# ATSAMD21G18A.net
KiCad netlist of a schematic drawn in Altium Designer
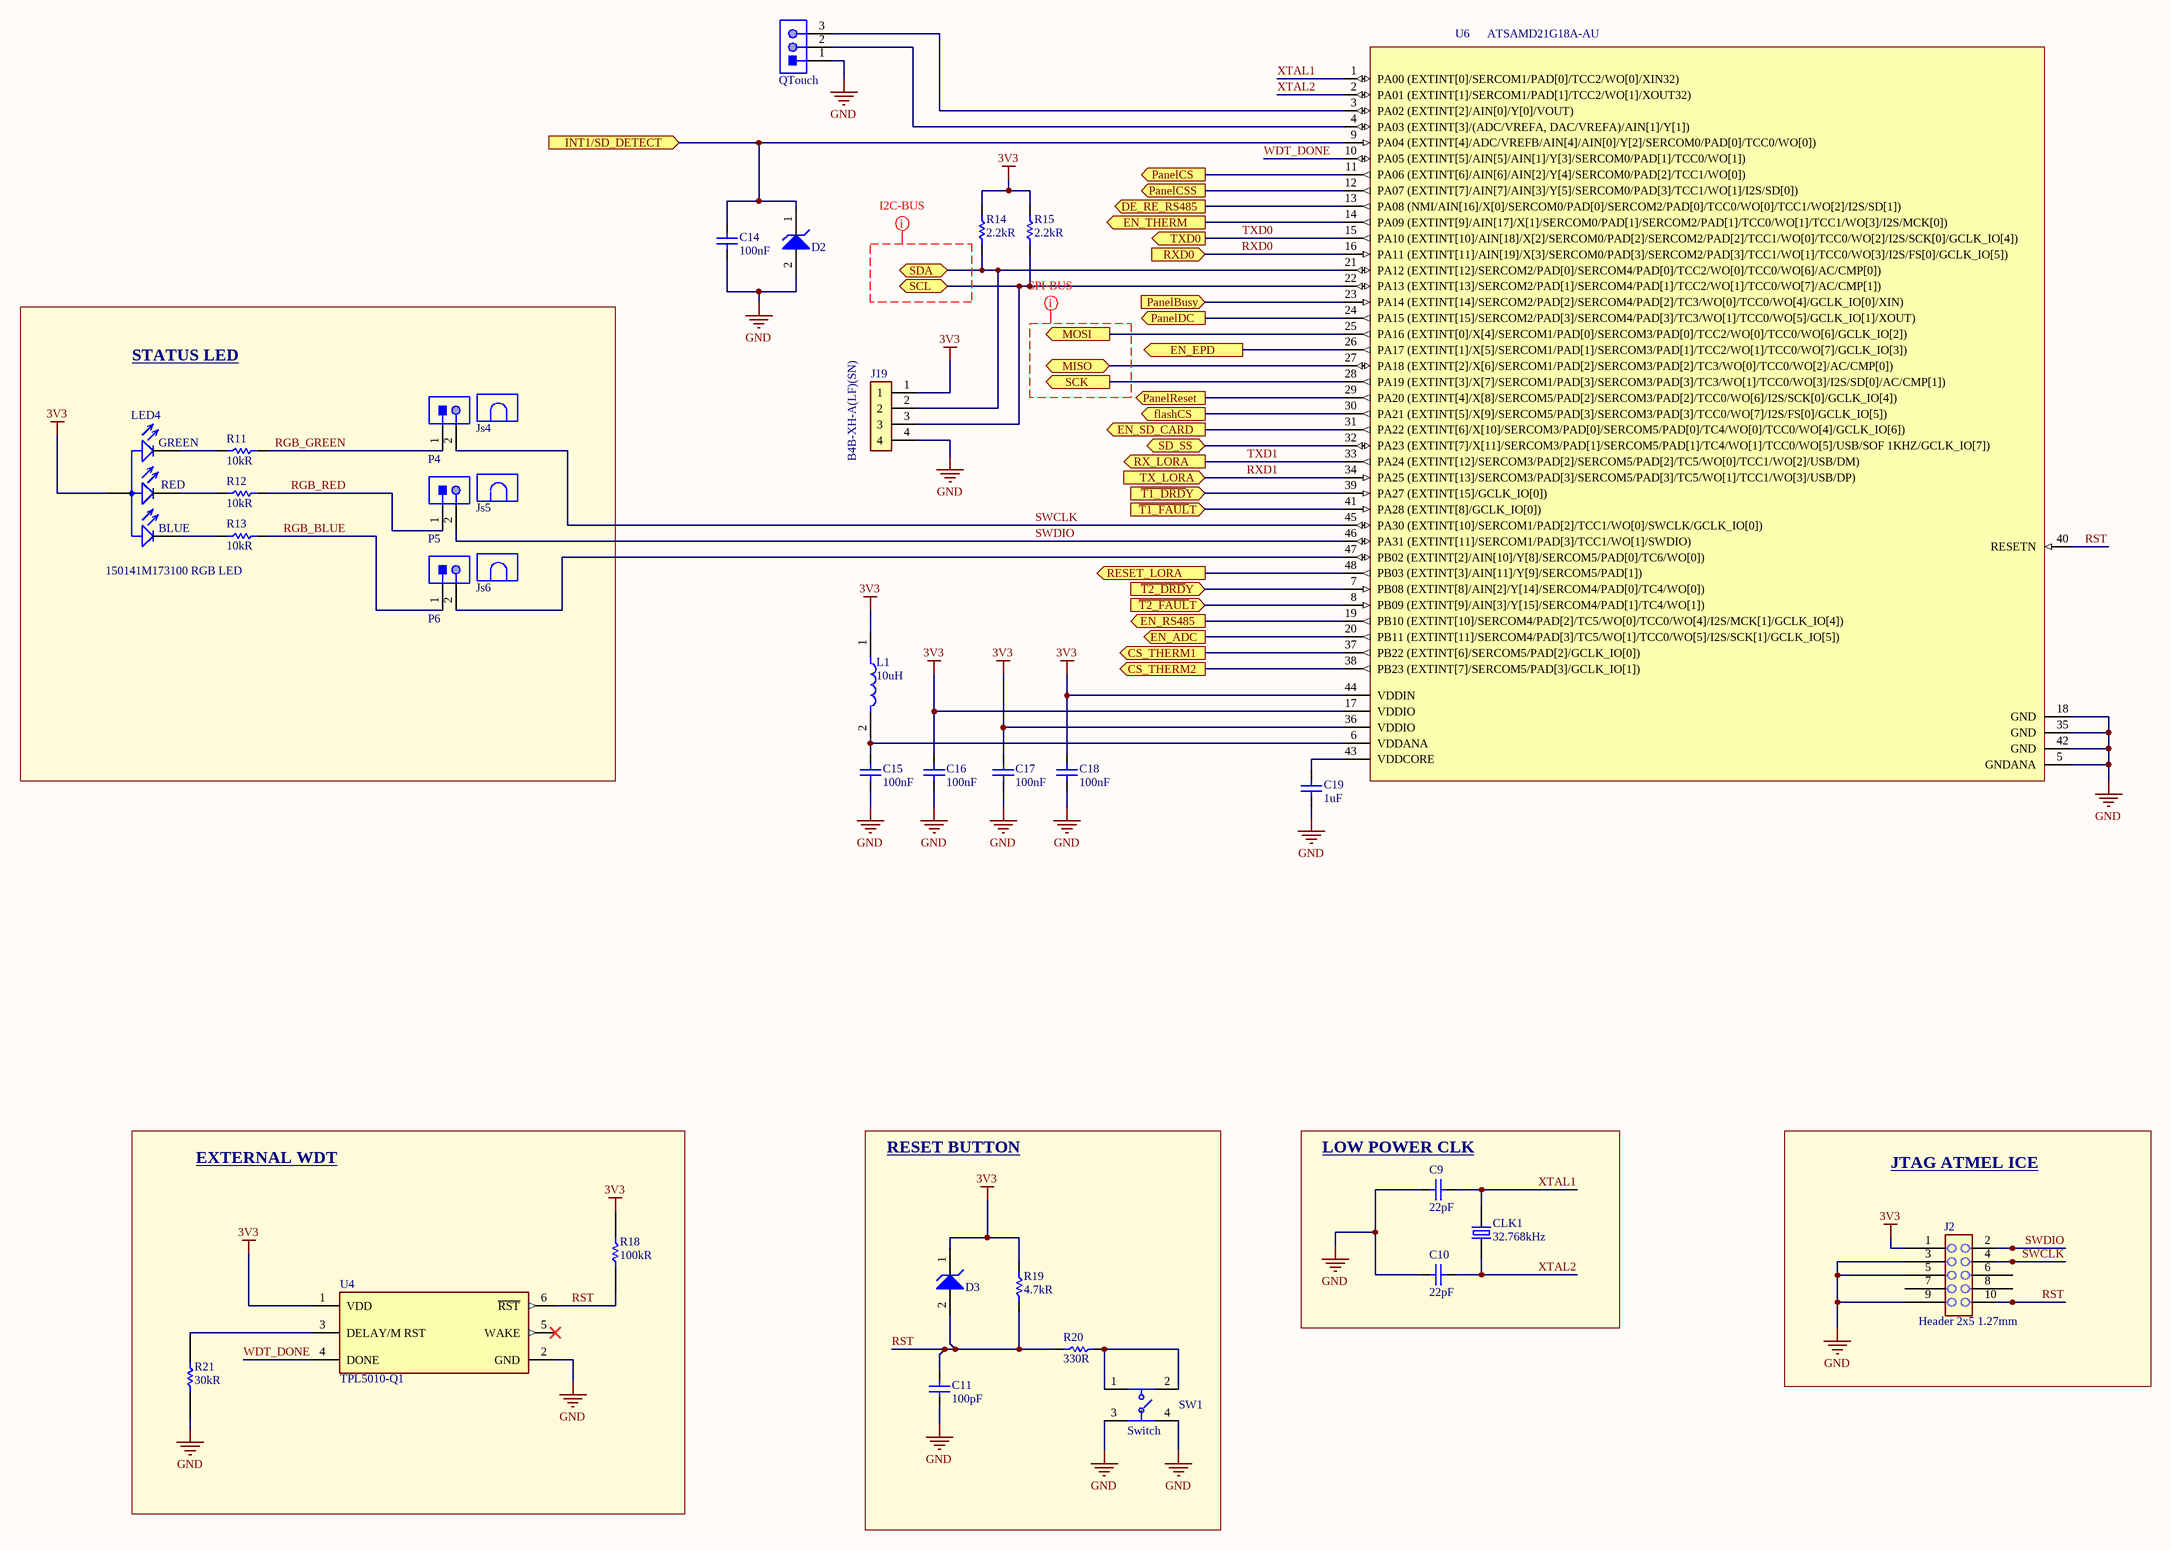
[diagram p0: ATSAMD21G18A.SchDoc]

(export (version "E")
  (design (tool "Eeschema 10.0.6"))
  (components
    (comp (ref "C9")
      (value "22pF")
      (footprint "Cap 0805 (2012 Metric)")
      (description "Capacitor; Ceramic; Cap; 22.0pF; Tol 5%; SMT; Vol-Rtg 50V; C0G; Tape and Reel")
      (fields
        (field (name "MANUFACTURER") "KEMET")
        (field (name "MANUFACTURER PART NUMBER") "C0805C220J5GACTU")
      )
      (libsource (lib "Daniel_Integrated_Library") (part "Capacitor"))
    )
    (comp (ref "C10")
      (value "22pF")
      (footprint "Cap 0805 (2012 Metric)")
      (description "Capacitor; Ceramic; Cap; 22.0pF; Tol 5%; SMT; Vol-Rtg 50V; C0G; Tape and Reel")
      (fields
        (field (name "MANUFACTURER") "KEMET")
        (field (name "MANUFACTURER PART NUMBER") "C0805C220J5GACTU")
      )
      (libsource (lib "Daniel_Integrated_Library") (part "Capacitor"))
    )
    (comp (ref "C11")
      (value "100pF")
      (footprint "Cap 0805 (2012 Metric)")
      (fields
        (field (name "MANUFACTURER") "KEMET")
        (field (name "MANUFACTURER PART NUMBER") "C0805C101J5GACTU")
        (field (name "TOLERANCE") "5%")
      )
      (libsource (lib "Daniel_Integrated_Library") (part "Capacitor"))
    )
    (comp (ref "C14")
      (value "100nF")
      (footprint "Cap 0805 (2012 Metric)")
      (fields
        (field (name "MANUFACTURER") "Yageo")
        (field (name "MANUFACTURER PART NUMBER") "CC0805ZRY5V9BB104")
        (field (name "TOLERANCE") "80%")
      )
      (libsource (lib "Daniel_Integrated_Library") (part "Capacitor"))
    )
    (comp (ref "C15")
      (value "100nF")
      (footprint "Cap 0805 (2012 Metric)")
      (fields
        (field (name "MANUFACTURER") "Yageo")
        (field (name "MANUFACTURER PART NUMBER") "CC0805ZRY5V9BB104")
        (field (name "TOLERANCE") "80%")
      )
      (libsource (lib "Daniel_Integrated_Library") (part "Capacitor"))
    )
    (comp (ref "C16")
      (value "100nF")
      (footprint "Cap 0805 (2012 Metric)")
      (fields
        (field (name "MANUFACTURER") "Yageo")
        (field (name "MANUFACTURER PART NUMBER") "CC0805ZRY5V9BB104")
        (field (name "TOLERANCE") "80%")
      )
      (libsource (lib "Daniel_Integrated_Library") (part "Capacitor"))
    )
    (comp (ref "C17")
      (value "100nF")
      (footprint "Cap 0805 (2012 Metric)")
      (fields
        (field (name "MANUFACTURER") "Yageo")
        (field (name "MANUFACTURER PART NUMBER") "CC0805ZRY5V9BB104")
        (field (name "TOLERANCE") "80%")
      )
      (libsource (lib "Daniel_Integrated_Library") (part "Capacitor"))
    )
    (comp (ref "C18")
      (value "100nF")
      (footprint "Cap 0805 (2012 Metric)")
      (fields
        (field (name "MANUFACTURER") "Yageo")
        (field (name "MANUFACTURER PART NUMBER") "CC0805ZRY5V9BB104")
        (field (name "TOLERANCE") "80%")
      )
      (libsource (lib "Daniel_Integrated_Library") (part "Capacitor"))
    )
    (comp (ref "C19")
      (value "1uF")
      (footprint "Cap 0805 (2012 Metric)")
      (description "Ceramic capacitor SMD-0805 1000nF /16V X7R# K +-10%, Samsung, RoHS/3000pcs/")
      (fields
        (field (name "MANUFACTURER") "Samsung")
        (field (name "MANUFACTURER PART NUMBER") "CL21B105KOFNNNG")
      )
      (libsource (lib "Daniel_Integrated_Library") (part "Capacitor"))
    )
    (comp (ref "CLK1")
      (value "ECS-327-12.5-13X")
      (footprint "ECS-327-12.5-13X")
      (description "CRYSTAL 32.7680KHZ 12.5PF T/H")
      (fields
        (field (name "MANUFACTURER") "ECS International")
        (field (name "MANUFACTURER PART NUMBER") "ECS-.327-12.5-13X")
        (field (name "FREQUENCY") "32.768kHz")
      )
      (libsource (lib "sebasLib") (part "ECS-327-12.5-13X"))
    )
    (comp (ref "D2")
      (value "Diode")
      (footprint "Diode SOD123")
      (description "DIODE GEN PURP 75V 150MA 0603")
      (fields
        (field (name "MANUFACTURER") "Taiwan Semiconductor")
        (field (name "MANUFACTURER PART NUMBER") "TS4148CRZG")
      )
      (libsource (lib "Daniel_Integrated_Library") (part "Diode"))
    )
    (comp (ref "D3")
      (value "Diode")
      (footprint "Diode SOD123")
      (description "DIODE GEN PURP 75V 150MA 0603")
      (fields
        (field (name "MANUFACTURER") "Taiwan Semiconductor")
        (field (name "MANUFACTURER PART NUMBER") "TS4148CRZG")
      )
      (libsource (lib "Daniel_Integrated_Library") (part "Diode"))
    )
    (comp (ref "J2")
      (value "Header 2x5 1.27mm")
      (footprint "HEADER_2X5_1-27mm_NO_CONNECTOR")
      (description "Connector Header Through Hole 10 position 0.050\" (1.27mm)")
      (fields
        (field (name "MANUFACTURER") "Adam Equipment")
        (field (name "MANUFACTURER PART NUMBER") "HPH2-A-10-UA")
      )
      (libsource (lib "Sebas_Integrated_Library") (part "Header 2x5 1.27mm"))
    )
    (comp (ref "J19")
      (value "B4B-XH-A(LF)(SN)")
      (footprint "B4B-XH-A(LF)(SN)")
      (fields (field (name "MANUFACTURER") "JST"))
      (libsource (lib "stratos") (part "B4B-XH-A(LF)(SN)"))
    )
    (comp (ref "Js4")
      (value "Jumper (2x1)")
      (footprint "Header JMP 2x1")
      (description "2 (1 x 2) Position Shunt Connector Black Open Top 0.100\" (2.54mm) Gold")
      (fields
        (field (name "MANUFACTURER") "Sullins")
        (field (name "MANUFACTURER PART NUMBER") "QPC02SXGN-RC")
      )
      (libsource (lib "Daniel_Integrated_Library") (part "Jumper (2x1)"))
    )
    (comp (ref "Js5")
      (value "Jumper (2x1)")
      (footprint "Header JMP 2x1")
      (description "2 (1 x 2) Position Shunt Connector Black Open Top 0.100\" (2.54mm) Gold")
      (fields
        (field (name "MANUFACTURER") "Sullins")
        (field (name "MANUFACTURER PART NUMBER") "QPC02SXGN-RC")
      )
      (libsource (lib "Daniel_Integrated_Library") (part "Jumper (2x1)"))
    )
    (comp (ref "Js6")
      (value "Jumper (2x1)")
      (footprint "Header JMP 2x1")
      (description "2 (1 x 2) Position Shunt Connector Black Open Top 0.100\" (2.54mm) Gold")
      (fields
        (field (name "MANUFACTURER") "Sullins")
        (field (name "MANUFACTURER PART NUMBER") "QPC02SXGN-RC")
      )
      (libsource (lib "Daniel_Integrated_Library") (part "Jumper (2x1)"))
    )
    (comp (ref "L1")
      (value "10uH")
      (footprint "Ind 0805 (2012 METRIC)")
      (fields
        (field (name "MANUFACTURER") "TDK")
        (field (name "MANUFACTURER PART NUMBER") "MLZ2012M100WT000")
        (field (name "TOLERANCE") "20%")
      )
      (libsource (lib "Daniel_Integrated_Library") (part "Inductor"))
    )
    (comp (ref "LED4")
      (value "150141M173100 RGB LED")
      (footprint "150141M173100")
      (description "Standard LEDs - SMD WL-SFTW SMDBiClr Top WL-SFTW")
      (fields
        (field (name "MANUFACTURER") "Wurth Electronics")
        (field (name "MANUFACTURER PART NUMBER") "150141M173100")
      )
      (libsource (lib "stratos") (part "150141M173100"))
    )
    (comp (ref "P4")
      (value "Header 2x1")
      (footprint "Header 2x1")
      (description "Connector Header Through Hole 2 position 0.100\" (2.54mm)")
      (fields
        (field (name "MANUFACTURER") "Amphenol FCI")
        (field (name "MANUFACTURER PART NUMBER") "68001-402HLF")
      )
      (libsource (lib "Daniel_Integrated_Library") (part "Header 2x1"))
    )
    (comp (ref "P5")
      (value "Header 2x1")
      (footprint "Header 2x1")
      (description "Connector Header Through Hole 2 position 0.100\" (2.54mm)")
      (fields
        (field (name "MANUFACTURER") "Amphenol FCI")
        (field (name "MANUFACTURER PART NUMBER") "68001-402HLF")
      )
      (libsource (lib "Daniel_Integrated_Library") (part "Header 2x1"))
    )
    (comp (ref "P6")
      (value "Header 2x1")
      (footprint "Header 2x1")
      (description "Connector Header Through Hole 2 position 0.100\" (2.54mm)")
      (fields
        (field (name "MANUFACTURER") "Amphenol FCI")
        (field (name "MANUFACTURER PART NUMBER") "68001-402HLF")
      )
      (libsource (lib "Daniel_Integrated_Library") (part "Header 2x1"))
    )
    (comp (ref "QTouch")
      (value "Header 3x1")
      (footprint "HEADER 3X1")
      (libsource (lib "Daniel_Integrated_Library") (part "Header 3x1"))
    )
    (comp (ref "R11")
      (value "10kR")
      (footprint "Res 0805 (2012 Metric)")
      (description "RES 10K OHM 1% 1/4W 0805")
      (fields
        (field (name "MANUFACTURER") "Stackpole Electronics")
        (field (name "MANUFACTURER PART NUMBER") "RNCP0805FTD10K0")
      )
      (libsource (lib "") (part "Resistor_1"))
    )
    (comp (ref "R12")
      (value "10kR")
      (footprint "Res 0805 (2012 Metric)")
      (description "RES 10K OHM 1% 1/4W 0805")
      (fields
        (field (name "MANUFACTURER") "Stackpole Electronics")
        (field (name "MANUFACTURER PART NUMBER") "RNCP0805FTD10K0")
      )
      (libsource (lib "") (part "Resistor_1"))
    )
    (comp (ref "R13")
      (value "10kR")
      (footprint "Res 0805 (2012 Metric)")
      (description "RES 10K OHM 1% 1/4W 0805")
      (fields
        (field (name "MANUFACTURER") "Stackpole Electronics")
        (field (name "MANUFACTURER PART NUMBER") "RNCP0805FTD10K0")
      )
      (libsource (lib "") (part "Resistor_1"))
    )
    (comp (ref "R14")
      (value "2.2kR")
      (footprint "Res 0805 (2012 Metric)")
      (description "Res Thick Film 0805 2.2K Ohm 5% 1/8W ±200ppm/°C Molded SMD SMD Paper T/R")
      (fields
        (field (name "MANUFACTURER") "Vishay Dale")
        (field (name "MANUFACTURER PART NUMBER") "CRCW08052K20JNEA")
      )
      (libsource (lib "") (part "Resistor_1"))
    )
    (comp (ref "R15")
      (value "2.2kR")
      (footprint "Res 0805 (2012 Metric)")
      (description "Res Thick Film 0805 2.2K Ohm 5% 1/8W ±200ppm/°C Molded SMD SMD Paper T/R")
      (fields
        (field (name "MANUFACTURER") "Vishay Dale")
        (field (name "MANUFACTURER PART NUMBER") "CRCW08052K20JNEA")
      )
      (libsource (lib "") (part "Resistor_1"))
    )
    (comp (ref "R18")
      (value "100kR")
      (footprint "Res 0805 (2012 Metric)")
      (description "YAGEO         RC0805FR-07100KL            RES, THICK FILM, 100K, 1%, 0.125W, 0805, REEL")
      (fields
        (field (name "MANUFACTURER") "Yageo")
        (field (name "MANUFACTURER PART NUMBER") "RC0805FR-07100KL")
      )
      (libsource (lib "Daniel_Integrated_Library") (part "Resistor"))
    )
    (comp (ref "R19")
      (value "4.7kR")
      (footprint "Res 0805 (2012 Metric)")
      (description "YAGEO - RC0805JR-074K7L. - RES, THICK FILM, 4K7, 5%, 0.125W, 0805")
      (fields
        (field (name "MANUFACTURER") "Yageo")
        (field (name "MANUFACTURER PART NUMBER") "RC0805JR-074K7L")
      )
      (libsource (lib "") (part "Resistor_1"))
    )
    (comp (ref "R20")
      (value "330R")
      (footprint "Res 0805 (2012 Metric)")
      (description "RES TF 1/8W 330 OHM 5% 0805")
      (fields
        (field (name "MANUFACTURER") "Stackpole Electronics")
        (field (name "MANUFACTURER PART NUMBER") "RMCF0805JT330R")
      )
      (libsource (lib "") (part "Resistor_1"))
    )
    (comp (ref "R21")
      (value "30kR")
      (footprint "Res 0805 (2012 Metric)")
      (description "Res Thick Film 0805 30K Ohm 1% 0.125W(1/8W) ±100ppm/C Epoxy SMD T/R")
      (fields
        (field (name "MANUFACTURER") "Yageo")
        (field (name "MANUFACTURER PART NUMBER") "RC0805FR-0730KL")
      )
      (libsource (lib "Daniel_Integrated_Library") (part "Resistor"))
    )
    (comp (ref "SW1")
      (value "Switch")
      (footprint "Sw 4 (4.5 X 4.5mm)")
      (description "Switch Tactile N.O. SPST Round Button Gull Wing 0.05A 12VDC 100000Cycles 2.45N SMD T/R")
      (fields
        (field (name "MANUFACTURER") "ITT C&K")
        (field (name "MANUFACTURER PART NUMBER") "PTS647SK38SMTR2LFS")
      )
      (libsource (lib "Daniel_Integrated_Library") (part "Switch"))
    )
    (comp (ref "U4")
      (value "TPL5010-Q1")
      (footprint "TPL5010-Q1_IPCA")
      (description "IC TIMER W/WATCHDOG 6-SOT")
      (fields
        (field (name "MANUFACTURER") "Texas Instruments")
        (field (name "MANUFACTURER PART NUMBER") "TPL5010QDDCTQ1")
      )
      (libsource (lib "Sebas_Integrated_Library") (part "TPL5010-Q1"))
    )
    (comp (ref "U6")
      (value "ATSAMD21G18A-AU-ND")
      (footprint "ATSAMD21G18A-AU-ND")
      (description "CORTEX-M0+, 256KB Flash, 32KB SRAM, Usb, Dma, T&r - 48TQFP Ind Temp, Green, 1.6-3.6V, 48MHZ")
      (fields
        (field (name "MANUFACTURER") "Microchip / Atmel")
        (field (name "MANUFACTURER PART NUMBER") "ATSAMD21G18A-AU")
      )
      (libsource (lib "stratos") (part "ATSAMD21G18A-AU"))
    )
  )
  (nets
    (net (code "1") (name "/CS_THERM1") (class "Default")
      (node (ref "U6") (pin "37") (pinfunction "PB22_(EXTINT[6]/SERCOM5/PAD[2]/GCLK_IO[0])_37") (pintype "output"))
    )
    (net (code "2") (name "/CS_THERM2") (class "Default")
      (node (ref "U6") (pin "38") (pinfunction "PB23_(EXTINT[7]/SERCOM5/PAD[3]/GCLK_IO[1])_38") (pintype "output"))
    )
    (net (code "3") (name "/DE_RE_RS485") (class "Default")
      (node (ref "U6") (pin "13") (pinfunction "PA08_(NMI/AIN[16]/X[0]/SERCOM0/PAD[0]/SERCOM2/PAD[0]/TCC0/WO[0]/TCC1/WO[2]/I2S/SD[1])_13") (pintype "output"))
    )
    (net (code "4") (name "/EN_ADC") (class "Default")
      (node (ref "U6") (pin "20") (pinfunction "PB11_(EXTINT[11]/SERCOM4/PAD[3]/TC5/WO[1]/TCC0/WO[5]/I2S/SCK[1]/GCLK_IO[5])_20") (pintype "output"))
    )
    (net (code "5") (name "/EN_EPD") (class "Default")
      (node (ref "U6") (pin "26") (pinfunction "PA17_(EXTINT[1]/X[5]/SERCOM1/PAD[1]/SERCOM3/PAD[1]/TCC2/WO[1]/TCC0/WO[7]/GCLK_IO[3])_26") (pintype "output"))
    )
    (net (code "6") (name "/EN_RS485") (class "Default")
      (node (ref "U6") (pin "19") (pinfunction "PB10_(EXTINT[10]/SERCOM4/PAD[2]/TC5/WO[0]/TCC0/WO[4]/I2S/MCK[1]/GCLK_IO[4])_19") (pintype "output"))
    )
    (net (code "7") (name "/EN_SD_CARD") (class "Default")
      (node (ref "U6") (pin "31") (pinfunction "PA22_(EXTINT[6]/X[10]/SERCOM3/PAD[0]/SERCOM5/PAD[0]/TC4/WO[0]/TCC0/WO[4]/GCLK_IO[6])_31") (pintype "output"))
    )
    (net (code "8") (name "/EN_THERM") (class "Default")
      (node (ref "U6") (pin "14") (pinfunction "PA09_(EXTINT[9]/AIN[17]/X[1]/SERCOM0/PAD[1]/SERCOM2/PAD[1]/TCC0/WO[1]/TCC1/WO[3]/I2S/MCK[0])_14") (pintype "output"))
    )
    (net (code "9") (name "/INT1{slash}SD_DETECT") (class "Default")
      (node (ref "C14") (pin "1") (pinfunction "1_1") (pintype "passive"))
      (node (ref "D2") (pin "1") (pinfunction "K_1") (pintype "passive"))
      (node (ref "U6") (pin "9") (pinfunction "PA04_(EXTINT[4]/ADC/VREFB/AIN[4]/AIN[0]/Y[2]/SERCOM0/PAD[0]/TCC0/WO[0])_9") (pintype "input"))
    )
    (net (code "10") (name "/MISO") (class "Default")
      (node (ref "U6") (pin "27") (pinfunction "PA18_(EXTINT[2]/X[6]/SERCOM1/PAD[2]/SERCOM3/PAD[2]/TC3/WO[0]/TCC0/WO[2]/AC/CMP[0])_27") (pintype "bidirectional"))
    )
    (net (code "11") (name "/MOSI") (class "Default")
      (node (ref "U6") (pin "25") (pinfunction "PA16_(EXTINT[0]/X[4]/SERCOM1/PAD[0]/SERCOM3/PAD[0]/TCC2/WO[0]/TCC0/WO[6]/GCLK_IO[2])_25") (pintype "output"))
    )
    (net (code "12") (name "/PanelBusy") (class "Default")
      (node (ref "U6") (pin "23") (pinfunction "PA14_(EXTINT[14]/SERCOM2/PAD[2]/SERCOM4/PAD[2]/TC3/WO[0]/TCC0/WO[4]/GCLK_IO[0]/XIN)_23") (pintype "input"))
    )
    (net (code "13") (name "/PanelCS") (class "Default")
      (node (ref "U6") (pin "11") (pinfunction "PA06_(EXTINT[6]/AIN[6]/AIN[2]/Y[4]/SERCOM0/PAD[2]/TCC1/WO[0])_11") (pintype "output"))
    )
    (net (code "14") (name "/PanelCSS") (class "Default")
      (node (ref "U6") (pin "12") (pinfunction "PA07_(EXTINT[7]/AIN[7]/AIN[3]/Y[5]/SERCOM0/PAD[3]/TCC1/WO[1]/I2S/SD[0])_12") (pintype "output"))
    )
    (net (code "15") (name "/PanelDC") (class "Default")
      (node (ref "U6") (pin "24") (pinfunction "PA15_(EXTINT[15]/SERCOM2/PAD[3]/SERCOM4/PAD[3]/TC3/WO[1]/TCC0/WO[5]/GCLK_IO[1]/XOUT)_24") (pintype "output"))
    )
    (net (code "16") (name "/PanelReset") (class "Default")
      (node (ref "U6") (pin "29") (pinfunction "PA20_(EXTINT[4]/X[8]/SERCOM5/PAD[2]/SERCOM3/PAD[2]/TCC0/WO[6]/I2S/SCK[0]/GCLK_IO[4])_29") (pintype "output"))
    )
    (net (code "17") (name "/RESET_LORA") (class "Default")
      (node (ref "U6") (pin "48") (pinfunction "PB03_(EXTINT[3]/AIN[11]/Y[9]/SERCOM5/PAD[1])_48") (pintype "output"))
    )
    (net (code "18") (name "/RGB_BLUE") (class "Default")
      (node (ref "P6") (pin "1") (pinfunction "1_1") (pintype "passive"))
      (node (ref "R13") (pin "2") (pinfunction "2_2") (pintype "passive"))
    )
    (net (code "19") (name "/RGB_GREEN") (class "Default")
      (node (ref "P4") (pin "1") (pinfunction "1_1") (pintype "passive"))
      (node (ref "R11") (pin "2") (pinfunction "2_2") (pintype "passive"))
    )
    (net (code "20") (name "/RGB_RED") (class "Default")
      (node (ref "P5") (pin "1") (pinfunction "1_1") (pintype "passive"))
      (node (ref "R12") (pin "2") (pinfunction "2_2") (pintype "passive"))
    )
    (net (code "21") (name "/RST") (class "Default")
      (node (ref "C11") (pin "1") (pinfunction "1_1") (pintype "passive"))
      (node (ref "D3") (pin "2") (pinfunction "A_2") (pintype "passive"))
      (node (ref "J2") (pin "10") (pinfunction "10_10") (pintype "passive"))
      (node (ref "R18") (pin "2") (pinfunction "2_2") (pintype "passive"))
      (node (ref "R19") (pin "2") (pinfunction "2_2") (pintype "passive"))
      (node (ref "R20") (pin "1") (pinfunction "1_1") (pintype "passive"))
      (node (ref "U4") (pin "6") (pinfunction "~{RST}_6") (pintype "output"))
      (node (ref "U6") (pin "40") (pinfunction "RESETN_40") (pintype "input"))
    )
    (net (code "22") (name "/RXD0") (class "Default")
      (node (ref "U6") (pin "16") (pinfunction "PA11_(EXTINT[11]/AIN[19]/X[3]/SERCOM0/PAD[3]/SERCOM2/PAD[3]/TCC1/WO[1]/TCC0/WO[3]/I2S/FS[0]/GCLK_IO[5])_16") (pintype "input"))
    )
    (net (code "23") (name "/RXD1") (class "Default")
      (node (ref "U6") (pin "34") (pinfunction "PA25_(EXTINT[13]/SERCOM3/PAD[3]/SERCOM5/PAD[3]/TC5/WO[1]/TCC1/WO[3]/USB/DP)_34") (pintype "input"))
    )
    (net (code "24") (name "/SCK") (class "Default")
      (node (ref "U6") (pin "28") (pinfunction "PA19_(EXTINT[3]/X[7]/SERCOM1/PAD[3]/SERCOM3/PAD[3]/TC3/WO[1]/TCC0/WO[3]/I2S/SD[0]/AC/CMP[1])_28") (pintype "output"))
    )
    (net (code "25") (name "/SCL") (class "Default")
      (node (ref "J19") (pin "3") (pinfunction "3_3") (pintype "passive"))
      (node (ref "R15") (pin "2") (pinfunction "2_2") (pintype "passive"))
      (node (ref "U6") (pin "22") (pinfunction "PA13_(EXTINT[13]/SERCOM2/PAD[1]/SERCOM4/PAD[1]/TCC2/WO[1]/TCC0/WO[7]/AC/CMP[1])_22") (pintype "bidirectional"))
    )
    (net (code "26") (name "/SDA") (class "Default")
      (node (ref "J19") (pin "2") (pinfunction "2_2") (pintype "passive"))
      (node (ref "R14") (pin "2") (pinfunction "2_2") (pintype "passive"))
      (node (ref "U6") (pin "21") (pinfunction "PA12_(EXTINT[12]/SERCOM2/PAD[0]/SERCOM4/PAD[0]/TCC2/WO[0]/TCC0/WO[6]/AC/CMP[0])_21") (pintype "bidirectional"))
    )
    (net (code "27") (name "/SD_SS") (class "Default")
      (node (ref "U6") (pin "32") (pinfunction "PA23_(EXTINT[7]/X[11]/SERCOM3/PAD[1]/SERCOM5/PAD[1]/TC4/WO[1]/TCC0/WO[5]/USB/SOF_1KHZ/GCLK_IO[7])_32") (pintype "bidirectional"))
    )
    (net (code "28") (name "/SWCLK") (class "Default")
      (node (ref "J2") (pin "4") (pinfunction "4_4") (pintype "passive"))
      (node (ref "P4") (pin "2") (pinfunction "2_2") (pintype "passive"))
      (node (ref "U6") (pin "45") (pinfunction "PA30_(EXTINT[10]/SERCOM1/PAD[2]/TCC1/WO[0]/SWCLK/GCLK_IO[0])_45") (pintype "bidirectional"))
    )
    (net (code "29") (name "/SWDIO") (class "Default")
      (node (ref "J2") (pin "2") (pinfunction "2_2") (pintype "passive"))
      (node (ref "P5") (pin "2") (pinfunction "2_2") (pintype "passive"))
      (node (ref "U6") (pin "46") (pinfunction "PA31_(EXTINT[11]/SERCOM1/PAD[3]/TCC1/WO[1]/SWDIO)_46") (pintype "bidirectional"))
    )
    (net (code "30") (name "/TXD0") (class "Default")
      (node (ref "U6") (pin "15") (pinfunction "PA10_(EXTINT[10]/AIN[18]/X[2]/SERCOM0/PAD[2]/SERCOM2/PAD[2]/TCC1/WO[0]/TCC0/WO[2]/I2S/SCK[0]/GCLK_IO[4])_15") (pintype "output"))
    )
    (net (code "31") (name "/TXD1") (class "Default")
      (node (ref "U6") (pin "33") (pinfunction "PA24_(EXTINT[12]/SERCOM3/PAD[2]/SERCOM5/PAD[2]/TC5/WO[0]/TCC1/WO[2]/USB/DM)_33") (pintype "output"))
    )
    (net (code "32") (name "/WDT_DONE") (class "Default")
      (node (ref "U4") (pin "4") (pinfunction "DONE_4") (pintype "passive"))
      (node (ref "U6") (pin "10") (pinfunction "PA05_(EXTINT[5]/AIN[5]/AIN[1]/Y[3]/SERCOM0/PAD[1]/TCC0/WO[1])_10") (pintype "bidirectional"))
    )
    (net (code "33") (name "/XTAL1") (class "Default")
      (node (ref "C9") (pin "2") (pinfunction "2_2") (pintype "passive"))
      (node (ref "CLK1") (pin "2") (pinfunction "2_2") (pintype "passive"))
      (node (ref "U6") (pin "1") (pinfunction "PA00_(EXTINT[0]/SERCOM1/PAD[0]/TCC2/WO[0]/XIN32)_1") (pintype "bidirectional"))
    )
    (net (code "34") (name "/XTAL2") (class "Default")
      (node (ref "C10") (pin "2") (pinfunction "2_2") (pintype "passive"))
      (node (ref "CLK1") (pin "1") (pinfunction "1_1") (pintype "passive"))
      (node (ref "U6") (pin "2") (pinfunction "PA01_(EXTINT[1]/SERCOM1/PAD[1]/TCC2/WO[1]/XOUT32)_2") (pintype "bidirectional"))
    )
    (net (code "35") (name "/flashCS") (class "Default")
      (node (ref "U6") (pin "30") (pinfunction "PA21_(EXTINT[5]/X[9]/SERCOM5/PAD[3]/SERCOM3/PAD[3]/TCC0/WO[7]/I2S/FS[0]/GCLK_IO[5])_30") (pintype "output"))
    )
    (net (code "36") (name "/~{T1_DRD}Y") (class "Default")
      (node (ref "U6") (pin "39") (pinfunction "PA27_(EXTINT[15]/GCLK_IO[0])_39") (pintype "input"))
    )
    (net (code "37") (name "/~{T1_FAUL}T") (class "Default")
      (node (ref "U6") (pin "41") (pinfunction "PA28_(EXTINT[8]/GCLK_IO[0])_41") (pintype "input"))
    )
    (net (code "38") (name "/~{T2_DRD}Y") (class "Default")
      (node (ref "U6") (pin "7") (pinfunction "PB08_(EXTINT[8]/AIN[2]/Y[14]/SERCOM4/PAD[0]/TC4/WO[0])_7") (pintype "input"))
    )
    (net (code "39") (name "/~{T2_FAUL}T") (class "Default")
      (node (ref "U6") (pin "8") (pinfunction "PB09_(EXTINT[9]/AIN[3]/Y[15]/SERCOM4/PAD[1]/TC4/WO[1])_8") (pintype "input"))
    )
    (net (code "40") (name "3V3") (class "Default")
      (node (ref "C16") (pin "1") (pinfunction "1_1") (pintype "passive"))
      (node (ref "C17") (pin "1") (pinfunction "1_1") (pintype "passive"))
      (node (ref "C18") (pin "1") (pinfunction "1_1") (pintype "passive"))
      (node (ref "D3") (pin "1") (pinfunction "K_1") (pintype "passive"))
      (node (ref "J19") (pin "1") (pinfunction "1_1") (pintype "passive"))
      (node (ref "J2") (pin "1") (pinfunction "1_1") (pintype "passive"))
      (node (ref "L1") (pin "1") (pinfunction "1_1") (pintype "passive"))
      (node (ref "LED4") (pin "1") (pinfunction "A_1") (pintype "passive"))
      (node (ref "R14") (pin "1") (pinfunction "1_1") (pintype "passive"))
      (node (ref "R15") (pin "1") (pinfunction "1_1") (pintype "passive"))
      (node (ref "R18") (pin "1") (pinfunction "1_1") (pintype "passive"))
      (node (ref "R19") (pin "1") (pinfunction "1_1") (pintype "passive"))
      (node (ref "U4") (pin "1") (pinfunction "VDD_1") (pintype "power_in"))
      (node (ref "U6") (pin "17") (pinfunction "VDDIO_17") (pintype "power_in"))
      (node (ref "U6") (pin "36") (pinfunction "VDDIO_36") (pintype "power_in"))
      (node (ref "U6") (pin "44") (pinfunction "VDDIN_44") (pintype "power_in"))
    )
    (net (code "41") (name "GND") (class "Default")
      (node (ref "C10") (pin "1") (pinfunction "1_1") (pintype "passive"))
      (node (ref "C11") (pin "2") (pinfunction "2_2") (pintype "passive"))
      (node (ref "C14") (pin "2") (pinfunction "2_2") (pintype "passive"))
      (node (ref "C15") (pin "2") (pinfunction "2_2") (pintype "passive"))
      (node (ref "C16") (pin "2") (pinfunction "2_2") (pintype "passive"))
      (node (ref "C17") (pin "2") (pinfunction "2_2") (pintype "passive"))
      (node (ref "C18") (pin "2") (pinfunction "2_2") (pintype "passive"))
      (node (ref "C19") (pin "2") (pinfunction "2_2") (pintype "passive"))
      (node (ref "C9") (pin "1") (pinfunction "1_1") (pintype "passive"))
      (node (ref "D2") (pin "2") (pinfunction "A_2") (pintype "passive"))
      (node (ref "J19") (pin "4") (pinfunction "4_4") (pintype "passive"))
      (node (ref "J2") (pin "3") (pinfunction "3_3") (pintype "passive"))
      (node (ref "J2") (pin "5") (pinfunction "5_5") (pintype "passive"))
      (node (ref "J2") (pin "9") (pinfunction "9_9") (pintype "passive"))
      (node (ref "QTouch") (pin "1") (pinfunction "1_1") (pintype "passive"))
      (node (ref "R21") (pin "2") (pinfunction "2_2") (pintype "passive"))
      (node (ref "SW1") (pin "3") (pinfunction "3_3") (pintype "passive"))
      (node (ref "SW1") (pin "4") (pinfunction "4_4") (pintype "passive"))
      (node (ref "U4") (pin "2") (pinfunction "GND_2") (pintype "power_in"))
      (node (ref "U6") (pin "18") (pinfunction "GND_18") (pintype "power_in"))
      (node (ref "U6") (pin "35") (pinfunction "GND_35") (pintype "power_in"))
      (node (ref "U6") (pin "42") (pinfunction "GND_42") (pintype "power_in"))
      (node (ref "U6") (pin "5") (pinfunction "GNDANA_5") (pintype "power_in"))
    )
    (net (code "42") (name "Net-(LED4-B_C)") (class "Default")
      (node (ref "LED4") (pin "2") (pinfunction "B_C_2") (pintype "passive"))
      (node (ref "R13") (pin "1") (pinfunction "1_1") (pintype "passive"))
    )
    (net (code "43") (name "Net-(LED4-G_C)") (class "Default")
      (node (ref "LED4") (pin "4") (pinfunction "G_C_4") (pintype "passive"))
      (node (ref "R11") (pin "1") (pinfunction "1_1") (pintype "passive"))
    )
    (net (code "44") (name "Net-(LED4-R_C)") (class "Default")
      (node (ref "LED4") (pin "3") (pinfunction "R_C_3") (pintype "passive"))
      (node (ref "R12") (pin "1") (pinfunction "1_1") (pintype "passive"))
    )
    (net (code "45") (name "Net-(R20-Pad2)") (class "Default")
      (node (ref "R20") (pin "2") (pinfunction "2_2") (pintype "passive"))
      (node (ref "SW1") (pin "1") (pinfunction "1_1") (pintype "passive"))
      (node (ref "SW1") (pin "2") (pinfunction "2_2") (pintype "passive"))
    )
    (net (code "46") (name "Net-(U4-DELAY{slash}M_RST)") (class "Default")
      (node (ref "R21") (pin "1") (pinfunction "1_1") (pintype "passive"))
      (node (ref "U4") (pin "3") (pinfunction "DELAY/M_RST_3") (pintype "passive"))
    )
    (net (code "47") (name "Net-(U6-PA02_(EXTINT[2]{slash}AIN[0]{slash}Y[0]{slash}VOUT))") (class "Default")
      (node (ref "QTouch") (pin "3") (pinfunction "3_3") (pintype "passive"))
      (node (ref "U6") (pin "3") (pinfunction "PA02_(EXTINT[2]/AIN[0]/Y[0]/VOUT)_3") (pintype "bidirectional"))
    )
    (net (code "48") (name "Net-(U6-PA03_(EXTINT[3]{slash}(ADC{slash}VREFA,_DAC{slash}VREFA){slash}AIN[1]{slash}Y[1]))") (class "Default")
      (node (ref "QTouch") (pin "2") (pinfunction "2_2") (pintype "passive"))
      (node (ref "U6") (pin "4") (pinfunction "PA03_(EXTINT[3]/(ADC/VREFA,_DAC/VREFA)/AIN[1]/Y[1])_4") (pintype "bidirectional"))
    )
    (net (code "49") (name "Net-(U6-PB02_(EXTINT[2]{slash}AIN[10]{slash}Y[8]{slash}SERCOM5{slash}PAD[0]{slash}TC6{slash}WO[0]))") (class "Default")
      (node (ref "P6") (pin "2") (pinfunction "2_2") (pintype "passive"))
      (node (ref "U6") (pin "47") (pinfunction "PB02_(EXTINT[2]/AIN[10]/Y[8]/SERCOM5/PAD[0]/TC6/WO[0])_47") (pintype "bidirectional"))
    )
    (net (code "50") (name "Net-(U6-VDDANA)") (class "Default")
      (node (ref "C15") (pin "1") (pinfunction "1_1") (pintype "passive"))
      (node (ref "L1") (pin "2") (pinfunction "2_2") (pintype "passive"))
      (node (ref "U6") (pin "6") (pinfunction "VDDANA_6") (pintype "power_in"))
    )
    (net (code "51") (name "Net-(U6-VDDCORE)") (class "Default")
      (node (ref "C19") (pin "1") (pinfunction "1_1") (pintype "passive"))
      (node (ref "U6") (pin "43") (pinfunction "VDDCORE_43") (pintype "power_in"))
    )
    (net (code "52") (name "unconnected-(J2-Pad6)") (class "Default")
      (node (ref "J2") (pin "6") (pinfunction "6_6") (pintype "passive"))
    )
    (net (code "53") (name "unconnected-(J2-Pad7)") (class "Default")
      (node (ref "J2") (pin "7") (pinfunction "7_7") (pintype "passive"))
    )
    (net (code "54") (name "unconnected-(J2-Pad8)") (class "Default")
      (node (ref "J2") (pin "8") (pinfunction "8_8") (pintype "passive"))
    )
    (net (code "55") (name "unconnected-(U4-WAKE-Pad5)") (class "Default")
      (node (ref "U4") (pin "5") (pinfunction "WAKE_5") (pintype "output+no_connect"))
    )
  )
)
